# RasPi-BplusHAT.net
KiCad netlist of a schematic drawn in EAGLE
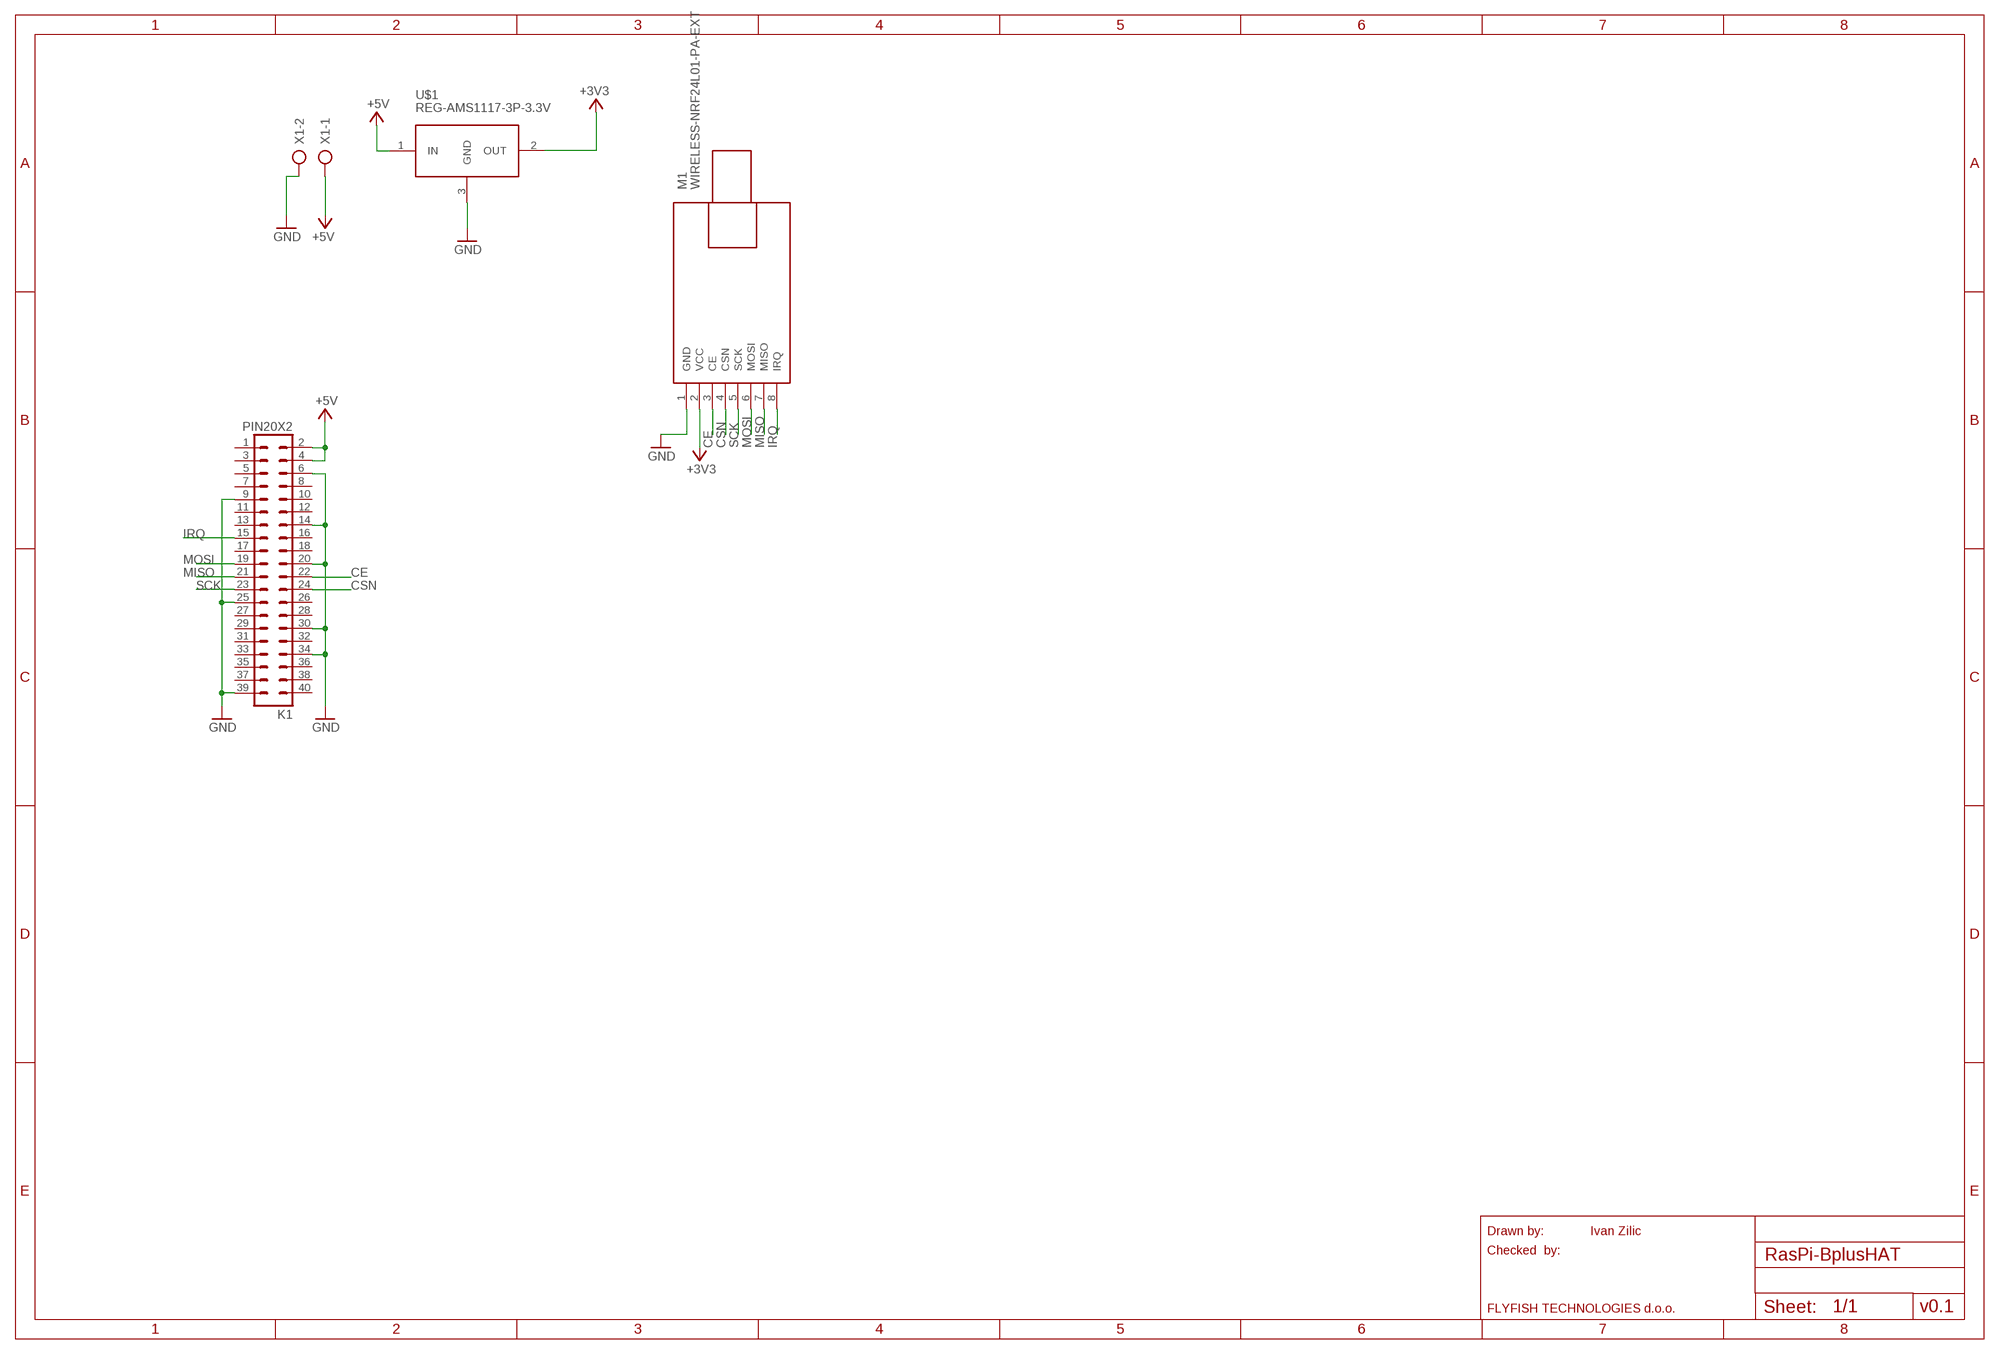
[diagram p0: schematic, sheet 1]

(export (version "E")
  (design (tool "Eeschema 10.0.6"))
  (components
    (comp (ref "K1")
      (value "PIN20X2")
      (footprint "eagle-import:PIN_20X2")
      (libsource (lib "eagle-import") (part "PIN20X2"))
    )
    (comp (ref "M1")
      (value "WIRELESS-NRF24L01-PA-EXT")
      (footprint "eagle-import:WIRELESS-NRF24L01-PA-EXT")
      (libsource (lib "eagle-import") (part "WIRELESS-NRF24L01-PA-EXT"))
    )
    (comp (ref "U$1")
      (value "REG-AMS1117-3P-3.3V")
      (footprint "eagle-import:REG-AMS1117-3P")
      (libsource (lib "eagle-import") (part "REG-AMS1117-3P-3.3V"))
    )
    (comp (ref "X1")
      (value "AK500/2")
      (footprint "eagle-import:AK500_2")
      (libsource (lib "eagle-import") (part "AK500/2"))
    )
  )
  (nets
    (net (code "1") (name "+3V3") (class "Default")
      (node (ref "M1") (pin "2") (pinfunction "VCC_2") (pintype "power_in"))
      (node (ref "U$1") (pin "2") (pinfunction "OUT_2") (pintype "bidirectional"))
    )
    (net (code "2") (name "+5V") (class "Default")
      (node (ref "K1") (pin "2") (pinfunction "2_2") (pintype "passive"))
      (node (ref "K1") (pin "4") (pinfunction "4_4") (pintype "passive"))
      (node (ref "U$1") (pin "1") (pinfunction "IN_1") (pintype "bidirectional"))
      (node (ref "X1") (pin "1") (pinfunction "KL_1") (pintype "passive"))
    )
    (net (code "3") (name "/CE") (class "Default")
      (node (ref "K1") (pin "22") (pinfunction "22_22") (pintype "passive"))
      (node (ref "M1") (pin "3") (pinfunction "CE_3") (pintype "bidirectional"))
    )
    (net (code "4") (name "/CSN") (class "Default")
      (node (ref "K1") (pin "24") (pinfunction "24_24") (pintype "passive"))
      (node (ref "M1") (pin "4") (pinfunction "CSN_4") (pintype "bidirectional"))
    )
    (net (code "5") (name "/IRQ") (class "Default")
      (node (ref "K1") (pin "15") (pinfunction "15_15") (pintype "passive"))
      (node (ref "M1") (pin "8") (pinfunction "IRQ_8") (pintype "bidirectional"))
    )
    (net (code "6") (name "/MISO") (class "Default")
      (node (ref "K1") (pin "21") (pinfunction "21_21") (pintype "passive"))
      (node (ref "M1") (pin "7") (pinfunction "MISO_7") (pintype "bidirectional"))
    )
    (net (code "7") (name "/MOSI") (class "Default")
      (node (ref "K1") (pin "19") (pinfunction "19_19") (pintype "passive"))
      (node (ref "M1") (pin "6") (pinfunction "MOSI_6") (pintype "bidirectional"))
    )
    (net (code "8") (name "/SCK") (class "Default")
      (node (ref "K1") (pin "23") (pinfunction "23_23") (pintype "passive"))
      (node (ref "M1") (pin "5") (pinfunction "SCK_5") (pintype "bidirectional"))
    )
    (net (code "9") (name "GND") (class "Default")
      (node (ref "K1") (pin "14") (pinfunction "14_14") (pintype "passive"))
      (node (ref "K1") (pin "20") (pinfunction "20_20") (pintype "passive"))
      (node (ref "K1") (pin "25") (pinfunction "25_25") (pintype "passive"))
      (node (ref "K1") (pin "30") (pinfunction "30_30") (pintype "passive"))
      (node (ref "K1") (pin "34") (pinfunction "34_34") (pintype "passive"))
      (node (ref "K1") (pin "39") (pinfunction "39_39") (pintype "passive"))
      (node (ref "K1") (pin "6") (pinfunction "6_6") (pintype "passive"))
      (node (ref "K1") (pin "9") (pinfunction "9_9") (pintype "passive"))
      (node (ref "M1") (pin "1") (pinfunction "GND_1") (pintype "power_in"))
      (node (ref "U$1") (pin "3") (pinfunction "GND_3") (pintype "bidirectional"))
      (node (ref "X1") (pin "2") (pinfunction "KL_2") (pintype "passive"))
    )
    (net (code "10") (name "unconnected-(K1-Pad1)") (class "Default")
      (node (ref "K1") (pin "1") (pinfunction "1_1") (pintype "passive"))
    )
    (net (code "11") (name "unconnected-(K1-Pad3)") (class "Default")
      (node (ref "K1") (pin "3") (pinfunction "3_3") (pintype "passive"))
    )
    (net (code "12") (name "unconnected-(K1-Pad5)") (class "Default")
      (node (ref "K1") (pin "5") (pinfunction "5_5") (pintype "passive"))
    )
    (net (code "13") (name "unconnected-(K1-Pad7)") (class "Default")
      (node (ref "K1") (pin "7") (pinfunction "7_7") (pintype "passive"))
    )
    (net (code "14") (name "unconnected-(K1-Pad8)") (class "Default")
      (node (ref "K1") (pin "8") (pinfunction "8_8") (pintype "passive"))
    )
    (net (code "15") (name "unconnected-(K1-Pad10)") (class "Default")
      (node (ref "K1") (pin "10") (pinfunction "10_10") (pintype "passive"))
    )
    (net (code "16") (name "unconnected-(K1-Pad11)") (class "Default")
      (node (ref "K1") (pin "11") (pinfunction "11_11") (pintype "passive"))
    )
    (net (code "17") (name "unconnected-(K1-Pad12)") (class "Default")
      (node (ref "K1") (pin "12") (pinfunction "12_12") (pintype "passive"))
    )
    (net (code "18") (name "unconnected-(K1-Pad13)") (class "Default")
      (node (ref "K1") (pin "13") (pinfunction "13_13") (pintype "passive"))
    )
    (net (code "19") (name "unconnected-(K1-Pad16)") (class "Default")
      (node (ref "K1") (pin "16") (pinfunction "16_16") (pintype "passive"))
    )
    (net (code "20") (name "unconnected-(K1-Pad17)") (class "Default")
      (node (ref "K1") (pin "17") (pinfunction "17_17") (pintype "passive"))
    )
    (net (code "21") (name "unconnected-(K1-Pad18)") (class "Default")
      (node (ref "K1") (pin "18") (pinfunction "18_18") (pintype "passive"))
    )
    (net (code "22") (name "unconnected-(K1-Pad26)") (class "Default")
      (node (ref "K1") (pin "26") (pinfunction "26_26") (pintype "passive"))
    )
    (net (code "23") (name "unconnected-(K1-Pad27)") (class "Default")
      (node (ref "K1") (pin "27") (pinfunction "27_27") (pintype "passive"))
    )
    (net (code "24") (name "unconnected-(K1-Pad28)") (class "Default")
      (node (ref "K1") (pin "28") (pinfunction "28_28") (pintype "passive"))
    )
    (net (code "25") (name "unconnected-(K1-Pad29)") (class "Default")
      (node (ref "K1") (pin "29") (pinfunction "29_29") (pintype "passive"))
    )
    (net (code "26") (name "unconnected-(K1-Pad31)") (class "Default")
      (node (ref "K1") (pin "31") (pinfunction "31_31") (pintype "passive"))
    )
    (net (code "27") (name "unconnected-(K1-Pad32)") (class "Default")
      (node (ref "K1") (pin "32") (pinfunction "32_32") (pintype "passive"))
    )
    (net (code "28") (name "unconnected-(K1-Pad33)") (class "Default")
      (node (ref "K1") (pin "33") (pinfunction "33_33") (pintype "passive"))
    )
    (net (code "29") (name "unconnected-(K1-Pad35)") (class "Default")
      (node (ref "K1") (pin "35") (pinfunction "35_35") (pintype "passive"))
    )
    (net (code "30") (name "unconnected-(K1-Pad36)") (class "Default")
      (node (ref "K1") (pin "36") (pinfunction "36_36") (pintype "passive"))
    )
    (net (code "31") (name "unconnected-(K1-Pad37)") (class "Default")
      (node (ref "K1") (pin "37") (pinfunction "37_37") (pintype "passive"))
    )
    (net (code "32") (name "unconnected-(K1-Pad38)") (class "Default")
      (node (ref "K1") (pin "38") (pinfunction "38_38") (pintype "passive"))
    )
    (net (code "33") (name "unconnected-(K1-Pad40)") (class "Default")
      (node (ref "K1") (pin "40") (pinfunction "40_40") (pintype "passive"))
    )
  )
)
